# design.net
KiCad netlist of a schematic drawn in Altium Designer
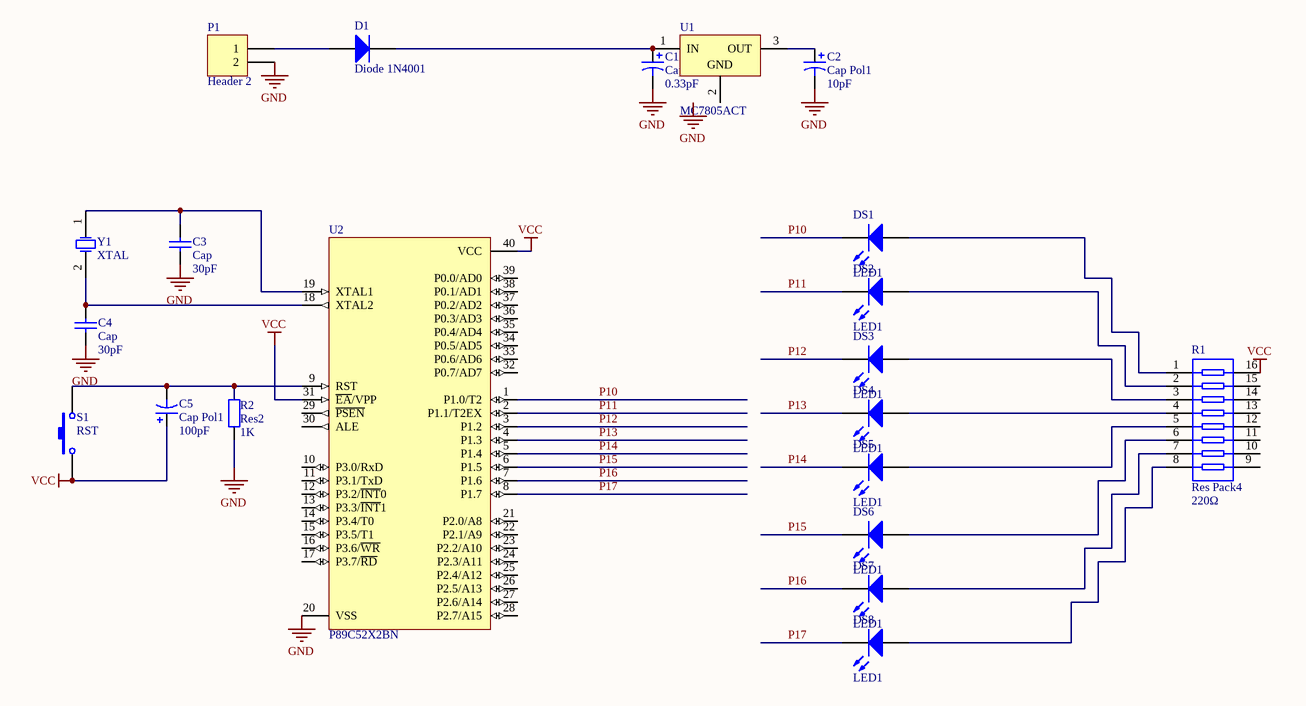
[diagram p0: 单片机控制流水灯电路.SchDoc]

(export (version "E")
  (design (tool "Eeschema 10.0.6"))
  (components
    (comp (ref "C1")
      (value "Cap Pol1")
      (footprint "RB7.6-15")
      (description "Polarized Capacitor (Radial)")
      (fields (field (name "ALTIUM_VALUE") "0.33pF") (field (name "PUBLISHER") "Altium Limited"))
      (libsource (lib "Miscellaneous Devices") (part "Cap Pol1"))
    )
    (comp (ref "C2")
      (value "Cap Pol1")
      (footprint "RB7.6-15")
      (description "Polarized Capacitor (Radial)")
      (fields (field (name "ALTIUM_VALUE") "10pF") (field (name "PUBLISHER") "Altium Limited"))
      (libsource (lib "Miscellaneous Devices") (part "Cap Pol1"))
    )
    (comp (ref "C3")
      (value "Cap")
      (footprint "RAD-0.3")
      (description "Capacitor")
      (fields (field (name "ALTIUM_VALUE") "30pF") (field (name "PUBLISHER") "Altium Limited"))
      (libsource (lib "Miscellaneous Devices") (part "Cap"))
    )
    (comp (ref "C4")
      (value "Cap")
      (footprint "RAD-0.3")
      (description "Capacitor")
      (fields (field (name "ALTIUM_VALUE") "30pF") (field (name "PUBLISHER") "Altium Limited"))
      (libsource (lib "Miscellaneous Devices") (part "Cap"))
    )
    (comp (ref "C5")
      (value "Cap Pol1")
      (footprint "RB7.6-15")
      (description "Polarized Capacitor (Radial)")
      (fields (field (name "ALTIUM_VALUE") "100pF") (field (name "PUBLISHER") "Altium Limited"))
      (libsource (lib "Miscellaneous Devices") (part "Cap Pol1"))
    )
    (comp (ref "D1")
      (value "Diode 1N4001")
      (footprint "DO-41")
      (description "1 Amp General Purpose Rectifier")
      (fields (field (name "PUBLISHER") "Altium Limited"))
      (libsource (lib "Miscellaneous Devices") (part "Diode 1N4001"))
    )
    (comp (ref "DS1")
      (value "LED1")
      (footprint "LED-1")
      (description "Typical RED GaAs LED")
      (fields (field (name "PUBLISHER") "Altium Limited"))
      (libsource (lib "Miscellaneous Devices") (part "LED1"))
    )
    (comp (ref "DS2")
      (value "LED1")
      (footprint "LED-1")
      (description "Typical RED GaAs LED")
      (fields (field (name "PUBLISHER") "Altium Limited"))
      (libsource (lib "Miscellaneous Devices") (part "LED1"))
    )
    (comp (ref "DS3")
      (value "LED1")
      (footprint "LED-1")
      (description "Typical RED GaAs LED")
      (fields (field (name "PUBLISHER") "Altium Limited"))
      (libsource (lib "Miscellaneous Devices") (part "LED1"))
    )
    (comp (ref "DS4")
      (value "LED1")
      (footprint "LED-1")
      (description "Typical RED GaAs LED")
      (fields (field (name "PUBLISHER") "Altium Limited"))
      (libsource (lib "Miscellaneous Devices") (part "LED1"))
    )
    (comp (ref "DS5")
      (value "LED1")
      (footprint "LED-1")
      (description "Typical RED GaAs LED")
      (fields (field (name "PUBLISHER") "Altium Limited"))
      (libsource (lib "Miscellaneous Devices") (part "LED1"))
    )
    (comp (ref "DS6")
      (value "LED1")
      (footprint "LED-1")
      (description "Typical RED GaAs LED")
      (fields (field (name "PUBLISHER") "Altium Limited"))
      (libsource (lib "Miscellaneous Devices") (part "LED1"))
    )
    (comp (ref "DS7")
      (value "LED1")
      (footprint "LED-1")
      (description "Typical RED GaAs LED")
      (fields (field (name "PUBLISHER") "Altium Limited"))
      (libsource (lib "Miscellaneous Devices") (part "LED1"))
    )
    (comp (ref "DS8")
      (value "LED1")
      (footprint "LED-1")
      (description "Typical RED GaAs LED")
      (fields (field (name "PUBLISHER") "Altium Limited"))
      (libsource (lib "Miscellaneous Devices") (part "LED1"))
    )
    (comp (ref "P1")
      (value "Header 2")
      (footprint "HDR1X2")
      (description "Header, 2-Pin")
      (fields (field (name "PUBLISHER") "Altium Limited"))
      (libsource (lib "Miscellaneous Connectors") (part "Header 2"))
    )
    (comp (ref "R1")
      (value "Res Pack4")
      (footprint "SSOP16_N")
      (description "Isolated Resistor Network")
      (fields (field (name "ALTIUM_VALUE") "220Ω") (field (name "PUBLISHER") "Altium Limited"))
      (libsource (lib "Miscellaneous Devices") (part "Res Pack4"))
    )
    (comp (ref "R2")
      (value "Res2")
      (footprint "AXIAL-0.4")
      (description "Resistor")
      (fields (field (name "ALTIUM_VALUE") "1K") (field (name "PUBLISHER") "Altium Limited"))
      (libsource (lib "Miscellaneous Devices") (part "Res2"))
    )
    (comp (ref "S1")
      (value "RST")
      (footprint "SPST-2")
      (description "Switch")
      (fields (field (name "PUBLISHER") "Altium Limited"))
      (libsource (lib "Miscellaneous Devices") (part "SW-PB"))
    )
    (comp (ref "U1")
      (value "MC7805ACT")
      (footprint "221A-04")
      (description "3-Terminal Positive Fixed Voltage Regulator")
      (fields (field (name "PUBLISHER") "Altium Limited"))
      (libsource (lib "Motorola Power Mgt Voltage Regulator") (part "MC7805ACT"))
    )
    (comp (ref "U2")
      (value "P89C52X2BN")
      (footprint "SOT129-1")
      (description "80C51 8-Bit Flash Microcontroller Family, 8 kB Flash")
      (fields (field (name "PUBLISHER") "Altium Limited"))
      (libsource (lib "Philips Microcontroller 8-Bit") (part "P89C52X2BN"))
    )
    (comp (ref "Y1")
      (value "XTAL")
      (footprint "R38")
      (description "Crystal Oscillator")
      (fields (field (name "PUBLISHER") "Altium Limited"))
      (libsource (lib "Miscellaneous Devices") (part "XTAL"))
    )
  )
  (nets
    (net (code "1") (name "/P10") (class "Default")
      (node (ref "DS1") (pin "2") (pinfunction "K_2") (pintype "passive"))
      (node (ref "U2") (pin "1") (pinfunction "P1.0/T2_1") (pintype "bidirectional"))
    )
    (net (code "2") (name "/P11") (class "Default")
      (node (ref "DS2") (pin "2") (pinfunction "K_2") (pintype "passive"))
      (node (ref "U2") (pin "2") (pinfunction "P1.1/T2EX_2") (pintype "bidirectional"))
    )
    (net (code "3") (name "/P12") (class "Default")
      (node (ref "DS3") (pin "2") (pinfunction "K_2") (pintype "passive"))
      (node (ref "U2") (pin "3") (pinfunction "P1.2_3") (pintype "bidirectional"))
    )
    (net (code "4") (name "/P13") (class "Default")
      (node (ref "DS4") (pin "2") (pinfunction "K_2") (pintype "passive"))
      (node (ref "U2") (pin "4") (pinfunction "P1.3_4") (pintype "bidirectional"))
    )
    (net (code "5") (name "/P14") (class "Default")
      (node (ref "DS5") (pin "2") (pinfunction "K_2") (pintype "passive"))
      (node (ref "U2") (pin "5") (pinfunction "P1.4_5") (pintype "bidirectional"))
    )
    (net (code "6") (name "/P15") (class "Default")
      (node (ref "DS6") (pin "2") (pinfunction "K_2") (pintype "passive"))
      (node (ref "U2") (pin "6") (pinfunction "P1.5_6") (pintype "bidirectional"))
    )
    (net (code "7") (name "/P16") (class "Default")
      (node (ref "DS7") (pin "2") (pinfunction "K_2") (pintype "passive"))
      (node (ref "U2") (pin "7") (pinfunction "P1.6_7") (pintype "bidirectional"))
    )
    (net (code "8") (name "/P17") (class "Default")
      (node (ref "DS8") (pin "2") (pinfunction "K_2") (pintype "passive"))
      (node (ref "U2") (pin "8") (pinfunction "P1.7_8") (pintype "bidirectional"))
    )
    (net (code "9") (name "GND") (class "Default")
      (node (ref "C1") (pin "2") (pinfunction "2_2") (pintype "passive"))
      (node (ref "C2") (pin "2") (pinfunction "2_2") (pintype "passive"))
      (node (ref "C3") (pin "1") (pinfunction "1_1") (pintype "passive"))
      (node (ref "C4") (pin "1") (pinfunction "1_1") (pintype "passive"))
      (node (ref "P1") (pin "2") (pinfunction "2_2") (pintype "passive"))
      (node (ref "R2") (pin "1") (pinfunction "1_1") (pintype "passive"))
      (node (ref "U2") (pin "20") (pinfunction "VSS_20") (pintype "power_in"))
    )
    (net (code "10") (name "Net-(D1-A)") (class "Default")
      (node (ref "D1") (pin "1") (pinfunction "A_1") (pintype "passive"))
      (node (ref "P1") (pin "1") (pinfunction "1_1") (pintype "passive"))
    )
    (net (code "11") (name "Net-(D1-K)") (class "Default")
      (node (ref "C1") (pin "1") (pinfunction "1_1") (pintype "passive"))
      (node (ref "D1") (pin "2") (pinfunction "K_2") (pintype "passive"))
      (node (ref "U1") (pin "1") (pinfunction "IN_1") (pintype "power_in"))
    )
    (net (code "12") (name "Net-(DS1-A)") (class "Default")
      (node (ref "DS1") (pin "1") (pinfunction "A_1") (pintype "passive"))
      (node (ref "R1") (pin "1") (pinfunction "1_1") (pintype "passive"))
    )
    (net (code "13") (name "Net-(DS2-A)") (class "Default")
      (node (ref "DS2") (pin "1") (pinfunction "A_1") (pintype "passive"))
      (node (ref "R1") (pin "2") (pinfunction "2_2") (pintype "passive"))
    )
    (net (code "14") (name "Net-(DS3-A)") (class "Default")
      (node (ref "DS3") (pin "1") (pinfunction "A_1") (pintype "passive"))
      (node (ref "R1") (pin "3") (pinfunction "3_3") (pintype "passive"))
    )
    (net (code "15") (name "Net-(DS4-A)") (class "Default")
      (node (ref "DS4") (pin "1") (pinfunction "A_1") (pintype "passive"))
      (node (ref "R1") (pin "4") (pinfunction "4_4") (pintype "passive"))
    )
    (net (code "16") (name "Net-(DS5-A)") (class "Default")
      (node (ref "DS5") (pin "1") (pinfunction "A_1") (pintype "passive"))
      (node (ref "R1") (pin "5") (pinfunction "5_5") (pintype "passive"))
    )
    (net (code "17") (name "Net-(DS6-A)") (class "Default")
      (node (ref "DS6") (pin "1") (pinfunction "A_1") (pintype "passive"))
      (node (ref "R1") (pin "6") (pinfunction "6_6") (pintype "passive"))
    )
    (net (code "18") (name "Net-(DS7-A)") (class "Default")
      (node (ref "DS7") (pin "1") (pinfunction "A_1") (pintype "passive"))
      (node (ref "R1") (pin "7") (pinfunction "7_7") (pintype "passive"))
    )
    (net (code "19") (name "Net-(DS8-A)") (class "Default")
      (node (ref "DS8") (pin "1") (pinfunction "A_1") (pintype "passive"))
      (node (ref "R1") (pin "8") (pinfunction "8_8") (pintype "passive"))
    )
    (net (code "20") (name "Net-(U1-OUT)") (class "Default")
      (node (ref "C2") (pin "1") (pinfunction "1_1") (pintype "passive"))
      (node (ref "U1") (pin "3") (pinfunction "OUT_3") (pintype "power_in"))
    )
    (net (code "21") (name "Net-(U2-RST)") (class "Default")
      (node (ref "C5") (pin "2") (pinfunction "2_2") (pintype "passive"))
      (node (ref "R2") (pin "2") (pinfunction "2_2") (pintype "passive"))
      (node (ref "S1") (pin "2") (pinfunction "2_2") (pintype "passive"))
      (node (ref "U2") (pin "9") (pinfunction "RST_9") (pintype "input"))
    )
    (net (code "22") (name "Net-(U2-XTAL1)") (class "Default")
      (node (ref "C3") (pin "2") (pinfunction "2_2") (pintype "passive"))
      (node (ref "U2") (pin "19") (pinfunction "XTAL1_19") (pintype "input"))
      (node (ref "Y1") (pin "1") (pinfunction "OSC1_1") (pintype "passive"))
    )
    (net (code "23") (name "Net-(U2-XTAL2)") (class "Default")
      (node (ref "C4") (pin "2") (pinfunction "2_2") (pintype "passive"))
      (node (ref "U2") (pin "18") (pinfunction "XTAL2_18") (pintype "output"))
      (node (ref "Y1") (pin "2") (pinfunction "OSC2_2") (pintype "passive"))
    )
    (net (code "24") (name "VCC") (class "Default")
      (node (ref "C5") (pin "1") (pinfunction "1_1") (pintype "passive"))
      (node (ref "R1") (pin "16") (pinfunction "16_16") (pintype "passive"))
      (node (ref "S1") (pin "1") (pinfunction "1_1") (pintype "passive"))
      (node (ref "U2") (pin "31") (pinfunction "~{EA}/VPP_31") (pintype "input"))
      (node (ref "U2") (pin "40") (pinfunction "VCC_40") (pintype "power_in"))
    )
    (net (code "25") (name "unconnected-(R1-Pad9)") (class "Default")
      (node (ref "R1") (pin "9") (pinfunction "9_9") (pintype "passive"))
    )
    (net (code "26") (name "unconnected-(R1-Pad10)") (class "Default")
      (node (ref "R1") (pin "10") (pinfunction "10_10") (pintype "passive"))
    )
    (net (code "27") (name "unconnected-(R1-Pad11)") (class "Default")
      (node (ref "R1") (pin "11") (pinfunction "11_11") (pintype "passive"))
    )
    (net (code "28") (name "unconnected-(R1-Pad12)") (class "Default")
      (node (ref "R1") (pin "12") (pinfunction "12_12") (pintype "passive"))
    )
    (net (code "29") (name "unconnected-(R1-Pad13)") (class "Default")
      (node (ref "R1") (pin "13") (pinfunction "13_13") (pintype "passive"))
    )
    (net (code "30") (name "unconnected-(R1-Pad14)") (class "Default")
      (node (ref "R1") (pin "14") (pinfunction "14_14") (pintype "passive"))
    )
    (net (code "31") (name "unconnected-(R1-Pad15)") (class "Default")
      (node (ref "R1") (pin "15") (pinfunction "15_15") (pintype "passive"))
    )
    (net (code "32") (name "unconnected-(U1-GND-Pad2)") (class "Default")
      (node (ref "U1") (pin "2") (pinfunction "GND_2") (pintype "power_in"))
    )
    (net (code "33") (name "unconnected-(U2-ALE-Pad30)") (class "Default")
      (node (ref "U2") (pin "30") (pinfunction "ALE_30") (pintype "output"))
    )
    (net (code "34") (name "unconnected-(U2-P0.0{slash}AD0-Pad39)") (class "Default")
      (node (ref "U2") (pin "39") (pinfunction "P0.0/AD0_39") (pintype "bidirectional"))
    )
    (net (code "35") (name "unconnected-(U2-P0.1{slash}AD1-Pad38)") (class "Default")
      (node (ref "U2") (pin "38") (pinfunction "P0.1/AD1_38") (pintype "bidirectional"))
    )
    (net (code "36") (name "unconnected-(U2-P0.2{slash}AD2-Pad37)") (class "Default")
      (node (ref "U2") (pin "37") (pinfunction "P0.2/AD2_37") (pintype "bidirectional"))
    )
    (net (code "37") (name "unconnected-(U2-P0.3{slash}AD3-Pad36)") (class "Default")
      (node (ref "U2") (pin "36") (pinfunction "P0.3/AD3_36") (pintype "bidirectional"))
    )
    (net (code "38") (name "unconnected-(U2-P0.4{slash}AD4-Pad35)") (class "Default")
      (node (ref "U2") (pin "35") (pinfunction "P0.4/AD4_35") (pintype "bidirectional"))
    )
    (net (code "39") (name "unconnected-(U2-P0.5{slash}AD5-Pad34)") (class "Default")
      (node (ref "U2") (pin "34") (pinfunction "P0.5/AD5_34") (pintype "bidirectional"))
    )
    (net (code "40") (name "unconnected-(U2-P0.6{slash}AD6-Pad33)") (class "Default")
      (node (ref "U2") (pin "33") (pinfunction "P0.6/AD6_33") (pintype "bidirectional"))
    )
    (net (code "41") (name "unconnected-(U2-P0.7{slash}AD7-Pad32)") (class "Default")
      (node (ref "U2") (pin "32") (pinfunction "P0.7/AD7_32") (pintype "bidirectional"))
    )
    (net (code "42") (name "unconnected-(U2-P2.0{slash}A8-Pad21)") (class "Default")
      (node (ref "U2") (pin "21") (pinfunction "P2.0/A8_21") (pintype "bidirectional"))
    )
    (net (code "43") (name "unconnected-(U2-P2.1{slash}A9-Pad22)") (class "Default")
      (node (ref "U2") (pin "22") (pinfunction "P2.1/A9_22") (pintype "bidirectional"))
    )
    (net (code "44") (name "unconnected-(U2-P2.2{slash}A10-Pad23)") (class "Default")
      (node (ref "U2") (pin "23") (pinfunction "P2.2/A10_23") (pintype "bidirectional"))
    )
    (net (code "45") (name "unconnected-(U2-P2.3{slash}A11-Pad24)") (class "Default")
      (node (ref "U2") (pin "24") (pinfunction "P2.3/A11_24") (pintype "bidirectional"))
    )
    (net (code "46") (name "unconnected-(U2-P2.4{slash}A12-Pad25)") (class "Default")
      (node (ref "U2") (pin "25") (pinfunction "P2.4/A12_25") (pintype "bidirectional"))
    )
    (net (code "47") (name "unconnected-(U2-P2.5{slash}A13-Pad26)") (class "Default")
      (node (ref "U2") (pin "26") (pinfunction "P2.5/A13_26") (pintype "bidirectional"))
    )
    (net (code "48") (name "unconnected-(U2-P2.6{slash}A14-Pad27)") (class "Default")
      (node (ref "U2") (pin "27") (pinfunction "P2.6/A14_27") (pintype "bidirectional"))
    )
    (net (code "49") (name "unconnected-(U2-P2.7{slash}A15-Pad28)") (class "Default")
      (node (ref "U2") (pin "28") (pinfunction "P2.7/A15_28") (pintype "bidirectional"))
    )
    (net (code "50") (name "unconnected-(U2-P3.0{slash}RxD-Pad10)") (class "Default")
      (node (ref "U2") (pin "10") (pinfunction "P3.0/RxD_10") (pintype "bidirectional"))
    )
    (net (code "51") (name "unconnected-(U2-P3.1{slash}TxD-Pad11)") (class "Default")
      (node (ref "U2") (pin "11") (pinfunction "P3.1/TxD_11") (pintype "bidirectional"))
    )
    (net (code "52") (name "unconnected-(U2-P3.2{slash}~{INT}0-Pad12)") (class "Default")
      (node (ref "U2") (pin "12") (pinfunction "P3.2/~{INT}0_12") (pintype "bidirectional"))
    )
    (net (code "53") (name "unconnected-(U2-P3.3{slash}~{INT}1-Pad13)") (class "Default")
      (node (ref "U2") (pin "13") (pinfunction "P3.3/~{INT}1_13") (pintype "bidirectional"))
    )
    (net (code "54") (name "unconnected-(U2-P3.4{slash}T0-Pad14)") (class "Default")
      (node (ref "U2") (pin "14") (pinfunction "P3.4/T0_14") (pintype "bidirectional"))
    )
    (net (code "55") (name "unconnected-(U2-P3.5{slash}T1-Pad15)") (class "Default")
      (node (ref "U2") (pin "15") (pinfunction "P3.5/T1_15") (pintype "bidirectional"))
    )
    (net (code "56") (name "unconnected-(U2-P3.6{slash}~{WR}-Pad16)") (class "Default")
      (node (ref "U2") (pin "16") (pinfunction "P3.6/~{WR}_16") (pintype "bidirectional"))
    )
    (net (code "57") (name "unconnected-(U2-P3.7{slash}~{RD}-Pad17)") (class "Default")
      (node (ref "U2") (pin "17") (pinfunction "P3.7/~{RD}_17") (pintype "bidirectional"))
    )
    (net (code "58") (name "unconnected-(U2-~{PSEN}-Pad29)") (class "Default")
      (node (ref "U2") (pin "29") (pinfunction "~{PSEN}_29") (pintype "output"))
    )
  )
)
